# LaserTagNeopixelBoard.net
KiCad netlist of a schematic drawn in Altium Designer
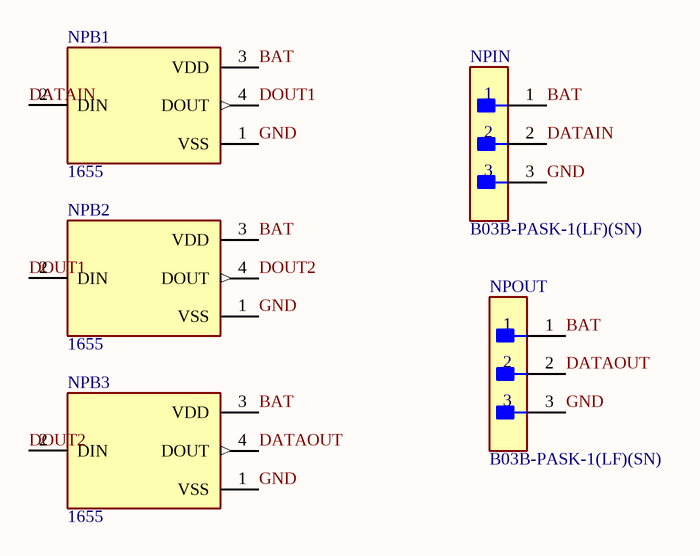
[diagram p0: LaserTagNeopixelBoard.SchDoc]

(export (version "E")
  (design (tool "Eeschema 10.0.6"))
  (components
    (comp (ref "NPB1")
      (value "1655")
      (footprint "LED_1655")
      (description "Ws2812b 5050 Rgb Led With Integrated Driver Chip Pack Of 10")
      (libsource (lib "1655") (part "1655"))
    )
    (comp (ref "NPB2")
      (value "1655")
      (footprint "LED_1655")
      (description "Ws2812b 5050 Rgb Led With Integrated Driver Chip Pack Of 10")
      (libsource (lib "1655") (part "1655"))
    )
    (comp (ref "NPB3")
      (value "1655")
      (footprint "LED_1655")
      (description "Ws2812b 5050 Rgb Led With Integrated Driver Chip Pack Of 10")
      (libsource (lib "1655") (part "1655"))
    )
    (comp (ref "NPIN")
      (value "B03B-PASK-1(LF)(SN)")
      (footprint "FP-B03B-PASK-1_LF_SN-MFG")
      (description "CONN HEADER VERT 3POS 2MM")
      (libsource (lib "Altium Content Vault") (part "0d3f023dd272f625e17a2be33dea85f"))
    )
    (comp (ref "NPOUT")
      (value "B03B-PASK-1(LF)(SN)")
      (footprint "FP-B03B-PASK-1_LF_SN-MFG")
      (description "CONN HEADER VERT 3POS 2MM")
      (libsource (lib "Altium Content Vault") (part "0d3f023dd272f625e17a2be33dea85f"))
    )
  )
  (nets
    (net (code "1") (name "/BAT") (class "Default")
      (node (ref "NPB1") (pin "3") (pinfunction "VDD_3") (pintype "power_in"))
      (node (ref "NPB2") (pin "3") (pinfunction "VDD_3") (pintype "power_in"))
      (node (ref "NPB3") (pin "3") (pinfunction "VDD_3") (pintype "power_in"))
      (node (ref "NPIN") (pin "1") (pinfunction "1_1") (pintype "passive"))
      (node (ref "NPOUT") (pin "1") (pinfunction "1_1") (pintype "passive"))
    )
    (net (code "2") (name "/DATAIN") (class "Default")
      (node (ref "NPB1") (pin "2") (pinfunction "DIN_2") (pintype "passive"))
      (node (ref "NPIN") (pin "2") (pinfunction "2_2") (pintype "passive"))
    )
    (net (code "3") (name "/DATAOUT") (class "Default")
      (node (ref "NPB3") (pin "4") (pinfunction "DOUT_4") (pintype "output"))
      (node (ref "NPOUT") (pin "2") (pinfunction "2_2") (pintype "passive"))
    )
    (net (code "4") (name "/DOUT1") (class "Default")
      (node (ref "NPB1") (pin "4") (pinfunction "DOUT_4") (pintype "output"))
      (node (ref "NPB2") (pin "2") (pinfunction "DIN_2") (pintype "passive"))
    )
    (net (code "5") (name "/DOUT2") (class "Default")
      (node (ref "NPB2") (pin "4") (pinfunction "DOUT_4") (pintype "output"))
      (node (ref "NPB3") (pin "2") (pinfunction "DIN_2") (pintype "passive"))
    )
    (net (code "6") (name "/GND") (class "Default")
      (node (ref "NPB1") (pin "1") (pinfunction "VSS_1") (pintype "power_in"))
      (node (ref "NPB2") (pin "1") (pinfunction "VSS_1") (pintype "power_in"))
      (node (ref "NPB3") (pin "1") (pinfunction "VSS_1") (pintype "power_in"))
      (node (ref "NPIN") (pin "3") (pinfunction "3_3") (pintype "passive"))
      (node (ref "NPOUT") (pin "3") (pinfunction "3_3") (pintype "passive"))
    )
  )
)
